# nightlight.net
KiCad netlist of a schematic drawn in EAGLE
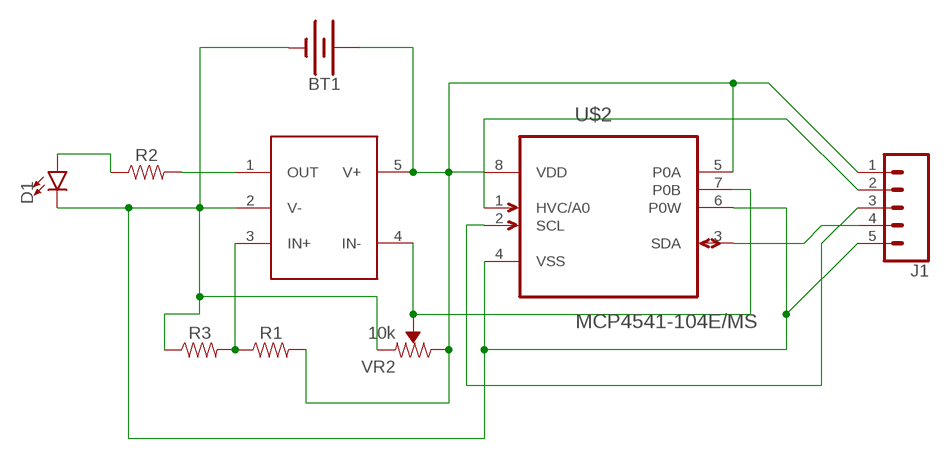
[diagram p0: schematic, sheet 1]

(export (version "E")
  (design (tool "Eeschema 10.0.6"))
  (components
    (comp (ref "BT1")
      (value "BATTERY-20MM_PTH")
      (footprint "eagle-import:BATTCOM_20MM_PTH")
      (libsource (lib "eagle-import") (part "BATTERY-20MM_PTH"))
    )
    (comp (ref "D1")
      (value "LED3MM")
      (footprint "eagle-import:LED_3MM")
      (libsource (lib "eagle-import") (part "LED3MM"))
    )
    (comp (ref "J1")
      (value "CONN_05PTH_LONGPADS")
      (footprint "eagle-import:1X05_LONGPADS")
      (libsource (lib "eagle-import") (part "CONN_05PTH_LONGPADS"))
    )
    (comp (ref "R1")
      (value "RESISTORAXIAL-0.3")
      (footprint "eagle-import:AXIAL-0.3")
      (libsource (lib "eagle-import") (part "RESISTORAXIAL-0.3"))
    )
    (comp (ref "R2")
      (value "RESISTORAXIAL-0.3")
      (footprint "eagle-import:AXIAL-0.3")
      (libsource (lib "eagle-import") (part "RESISTORAXIAL-0.3"))
    )
    (comp (ref "R3")
      (value "RESISTORAXIAL-0.3")
      (footprint "eagle-import:AXIAL-0.3")
      (libsource (lib "eagle-import") (part "RESISTORAXIAL-0.3"))
    )
    (comp (ref "U$1")
      (value "TLV8801DBVT")
      (footprint "eagle-import:SOT95P280X145-5N")
      (libsource (lib "eagle-import") (part "TLV8801DBVT"))
    )
    (comp (ref "U$2")
      (value "MCP4541-104E/MS")
      (footprint "eagle-import:SOP65P490X110-8N")
      (libsource (lib "eagle-import") (part "MCP4541-104E/MS"))
    )
    (comp (ref "VR2")
      (value "10k")
      (footprint "eagle-import:TRIMPOT-PTH-3386U")
      (libsource (lib "eagle-import") (part "TRIMPOT-PTH-10MM-KNOB-1/2W-10%"))
    )
  )
  (nets
    (net (code "1") (name "Net-(BT1-+)") (class "Default")
      (node (ref "BT1") (pin "1") (pinfunction "+_1") (pintype "power_in"))
      (node (ref "J1") (pin "1") (pinfunction "1_1") (pintype "passive"))
      (node (ref "R1") (pin "P$2") (pinfunction "2_P$2") (pintype "passive"))
      (node (ref "U$1") (pin "5") (pinfunction "V+_5") (pintype "bidirectional"))
      (node (ref "U$2") (pin "5") (pinfunction "P0A_5") (pintype "passive"))
      (node (ref "U$2") (pin "8") (pinfunction "VDD_8") (pintype "power_in"))
      (node (ref "VR2") (pin "3") (pinfunction "CW_3") (pintype "passive"))
    )
    (net (code "2") (name "Net-(BT1--)") (class "Default")
      (node (ref "BT1") (pin "2") (pinfunction "-_2") (pintype "power_in"))
      (node (ref "D1") (pin "K") (pinfunction "C_K") (pintype "passive"))
      (node (ref "J1") (pin "5") (pinfunction "5_5") (pintype "passive"))
      (node (ref "R3") (pin "P$1") (pinfunction "1_P$1") (pintype "passive"))
      (node (ref "U$1") (pin "2") (pinfunction "V-_2") (pintype "bidirectional"))
      (node (ref "U$2") (pin "4") (pinfunction "VSS_4") (pintype "power_in"))
      (node (ref "U$2") (pin "6") (pinfunction "P0W_6") (pintype "passive"))
      (node (ref "VR2") (pin "1") (pinfunction "CCW_1") (pintype "passive"))
    )
    (net (code "3") (name "Net-(R1-1)") (class "Default")
      (node (ref "R1") (pin "P$1") (pinfunction "1_P$1") (pintype "passive"))
      (node (ref "R3") (pin "P$2") (pinfunction "2_P$2") (pintype "passive"))
      (node (ref "U$1") (pin "3") (pinfunction "IN+_3") (pintype "bidirectional"))
    )
    (net (code "4") (name "Net-(R2-1)") (class "Default")
      (node (ref "D1") (pin "A") (pinfunction "A_A") (pintype "passive"))
      (node (ref "R2") (pin "P$1") (pinfunction "1_P$1") (pintype "passive"))
    )
    (net (code "5") (name "Net-(R2-2)") (class "Default")
      (node (ref "R2") (pin "P$2") (pinfunction "2_P$2") (pintype "passive"))
      (node (ref "U$1") (pin "1") (pinfunction "OUT_1") (pintype "bidirectional"))
    )
    (net (code "6") (name "Net-(U$1-IN-)") (class "Default")
      (node (ref "U$1") (pin "4") (pinfunction "IN-_4") (pintype "bidirectional"))
      (node (ref "U$2") (pin "7") (pinfunction "P0B_7") (pintype "passive"))
      (node (ref "VR2") (pin "2") (pinfunction "WIPER_2") (pintype "passive"))
    )
    (net (code "7") (name "Net-(U$2-HVC{slash}A0)") (class "Default")
      (node (ref "J1") (pin "2") (pinfunction "2_2") (pintype "passive"))
      (node (ref "U$2") (pin "1") (pinfunction "HVC/A0_1") (pintype "input"))
    )
    (net (code "8") (name "Net-(U$2-SCL)") (class "Default")
      (node (ref "J1") (pin "3") (pinfunction "3_3") (pintype "passive"))
      (node (ref "U$2") (pin "2") (pinfunction "SCL_2") (pintype "input"))
    )
    (net (code "9") (name "Net-(U$2-SDA)") (class "Default")
      (node (ref "J1") (pin "4") (pinfunction "4_4") (pintype "passive"))
      (node (ref "U$2") (pin "3") (pinfunction "SDA_3") (pintype "bidirectional"))
    )
  )
)
